# UART_USB.net
KiCad netlist of a schematic drawn in Altium Designer
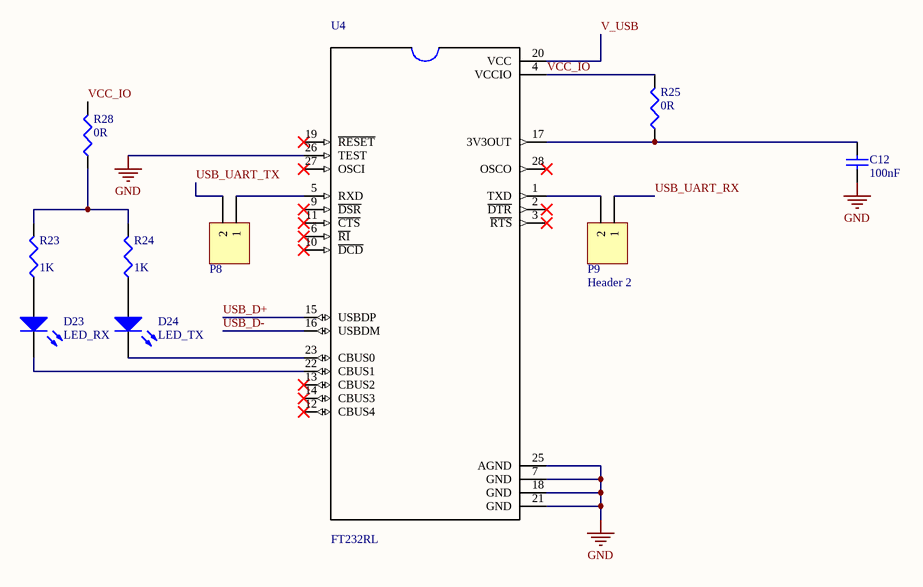
[diagram p0: UART_USB.SchDoc]

(export (version "E")
  (design (tool "Eeschema 10.0.6"))
  (components
    (comp (ref "C12")
      (value "100nF")
      (footprint "1608[0603]")
      (description "CAP CER 0.1UF 16V X7R 0603")
      (fields
        (field (name "DIGI-KEY PART NUMBER") "1276-1258-1-ND")
        (field (name "MANUFACTURER") "Samsung Electro-Mechanics")
        (field (name "PUBLISHER") "Altium Limited")
      )
      (libsource (lib "Miscellaneous Devices") (part "Cap"))
    )
    (comp (ref "D23")
      (value "LED_RX")
      (footprint "1608[0603]")
      (description "LED RED DIFFUSED 0603 SMD")
      (fields
        (field (name "DIGI-KEY PART NUMBER") "475-1195-1-ND")
        (field (name "MANUFACTURER") "OSRAM Opto Semiconductors Inc.")
      )
      (libsource (lib "Miscellaneous Devices") (part "LED2"))
    )
    (comp (ref "D24")
      (value "LED_TX")
      (footprint "1608[0603]")
      (description "LED YELLOW DIFFUSED 0603 SMD")
      (fields
        (field (name "DIGI-KEY PART NUMBER") "475-1196-1-ND")
        (field (name "MANUFACTURER") "OSRAM Opto Semiconductors Inc.")
      )
      (libsource (lib "Miscellaneous Devices") (part "LED2"))
    )
    (comp (ref "P8")
      (value "Header 2")
      (footprint "HDR1X2")
      (description "Header, 2-Pin")
      (fields (field (name "PUBLISHER") "Altium Limited"))
      (libsource (lib "Miscellaneous Connectors") (part "Header 2"))
    )
    (comp (ref "P9")
      (value "Header 2")
      (footprint "HDR1X2")
      (description "Header, 2-Pin")
      (fields (field (name "PUBLISHER") "Altium Limited"))
      (libsource (lib "Miscellaneous Connectors") (part "Header 2"))
    )
    (comp (ref "R23")
      (value "1K")
      (footprint "1608[0603]")
      (description "RES SMD 1K OHM 1% 1/8W 0603")
      (fields
        (field (name "DIGI-KEY PART NUMBER") "MCT0603-1.00K-CFCT-ND")
        (field (name "MANUFACTURER") "Vishay Beyschlag")
      )
      (libsource (lib "Miscellaneous Devices") (part "Res3"))
    )
    (comp (ref "R24")
      (value "1K")
      (footprint "1608[0603]")
      (description "RES SMD 1K OHM 1% 1/8W 0603")
      (fields
        (field (name "DIGI-KEY PART NUMBER") "MCT0603-1.00K-CFCT-ND")
        (field (name "MANUFACTURER") "Vishay Beyschlag")
      )
      (libsource (lib "Miscellaneous Devices") (part "Res3"))
    )
    (comp (ref "R25")
      (value "0R")
      (footprint "C1206")
      (description "RES 0 OHM JUMPER 1/8W 0603")
      (fields
        (field (name "DIGI-KEY PART NUMBER") "749-1745-1-ND")
        (field (name "MANUFACTURER") "Vishay Beyschlag")
      )
      (libsource (lib "Miscellaneous Devices") (part "Res3"))
    )
    (comp (ref "R28")
      (value "0R")
      (footprint "C1206")
      (description "RES 0 OHM JUMPER 1/8W 0603")
      (fields
        (field (name "DIGI-KEY PART NUMBER") "749-1745-1-ND")
        (field (name "MANUFACTURER") "Vishay Beyschlag")
      )
      (libsource (lib "Miscellaneous Devices") (part "Res3"))
    )
    (comp (ref "U4")
      (value "FT232RL")
      (footprint "SOP65P780X200-28N")
      (description "USB Bridge, USB to UART USB 2.0 UART Interface 28-SSOP")
      (fields (field (name "MP") "FT232RL-REEL") (field (name "MF") "FTDI,"))
      (libsource (lib "FT232RL-REEL") (part "FT232RL-REEL"))
    )
  )
  (nets
    (net (code "1") (name "/USB_D+") (class "Default")
      (node (ref "U4") (pin "15") (pinfunction "USBDP_15") (pintype "bidirectional"))
    )
    (net (code "2") (name "/USB_D-") (class "Default")
      (node (ref "U4") (pin "16") (pinfunction "USBDM_16") (pintype "bidirectional"))
    )
    (net (code "3") (name "/USB_UART_RX") (class "Default")
      (node (ref "P9") (pin "1") (pinfunction "1_1") (pintype "passive"))
    )
    (net (code "4") (name "/USB_UART_TX") (class "Default")
      (node (ref "P8") (pin "2") (pinfunction "2_2") (pintype "passive"))
    )
    (net (code "5") (name "/VCC_IO") (class "Default")
      (node (ref "R25") (pin "2") (pinfunction "2_2") (pintype "passive"))
      (node (ref "R28") (pin "2") (pinfunction "2_2") (pintype "passive"))
      (node (ref "U4") (pin "4") (pinfunction "VCCIO_4") (pintype "power_in"))
    )
    (net (code "6") (name "/V_USB") (class "Default")
      (node (ref "U4") (pin "20") (pinfunction "VCC_20") (pintype "power_in"))
    )
    (net (code "7") (name "GND") (class "Default")
      (node (ref "C12") (pin "2") (pinfunction "2_2") (pintype "passive"))
      (node (ref "U4") (pin "18") (pinfunction "GND_18") (pintype "passive"))
      (node (ref "U4") (pin "21") (pinfunction "GND_21") (pintype "passive"))
      (node (ref "U4") (pin "25") (pinfunction "AGND_25") (pintype "passive"))
      (node (ref "U4") (pin "26") (pinfunction "TEST_26") (pintype "input"))
      (node (ref "U4") (pin "7") (pinfunction "GND_7") (pintype "passive"))
    )
    (net (code "8") (name "Net-(D23-A)") (class "Default")
      (node (ref "D23") (pin "1") (pinfunction "A_1") (pintype "passive"))
      (node (ref "R23") (pin "1") (pinfunction "1_1") (pintype "passive"))
    )
    (net (code "9") (name "Net-(D23-K)") (class "Default")
      (node (ref "D23") (pin "2") (pinfunction "K_2") (pintype "passive"))
      (node (ref "U4") (pin "22") (pinfunction "CBUS1_22") (pintype "bidirectional"))
    )
    (net (code "10") (name "Net-(D24-A)") (class "Default")
      (node (ref "D24") (pin "1") (pinfunction "A_1") (pintype "passive"))
      (node (ref "R24") (pin "1") (pinfunction "1_1") (pintype "passive"))
    )
    (net (code "11") (name "Net-(D24-K)") (class "Default")
      (node (ref "D24") (pin "2") (pinfunction "K_2") (pintype "passive"))
      (node (ref "U4") (pin "23") (pinfunction "CBUS0_23") (pintype "bidirectional"))
    )
    (net (code "12") (name "Net-(R23-Pad2)") (class "Default")
      (node (ref "R23") (pin "2") (pinfunction "2_2") (pintype "passive"))
      (node (ref "R24") (pin "2") (pinfunction "2_2") (pintype "passive"))
      (node (ref "R28") (pin "1") (pinfunction "1_1") (pintype "passive"))
    )
    (net (code "13") (name "Net-(U4-3V3OUT)") (class "Default")
      (node (ref "C12") (pin "1") (pinfunction "1_1") (pintype "passive"))
      (node (ref "R25") (pin "1") (pinfunction "1_1") (pintype "passive"))
      (node (ref "U4") (pin "17") (pinfunction "3V3OUT_17") (pintype "output"))
    )
    (net (code "14") (name "Net-(U4-RXD)") (class "Default")
      (node (ref "P8") (pin "1") (pinfunction "1_1") (pintype "passive"))
      (node (ref "U4") (pin "5") (pinfunction "RXD_5") (pintype "input"))
    )
    (net (code "15") (name "Net-(U4-TXD)") (class "Default")
      (node (ref "P9") (pin "2") (pinfunction "2_2") (pintype "passive"))
      (node (ref "U4") (pin "1") (pinfunction "TXD_1") (pintype "output"))
    )
    (net (code "16") (name "unconnected-(U4-CBUS2-Pad13)") (class "Default")
      (node (ref "U4") (pin "13") (pinfunction "CBUS2_13") (pintype "bidirectional+no_connect"))
    )
    (net (code "17") (name "unconnected-(U4-CBUS3-Pad14)") (class "Default")
      (node (ref "U4") (pin "14") (pinfunction "CBUS3_14") (pintype "bidirectional+no_connect"))
    )
    (net (code "18") (name "unconnected-(U4-CBUS4-Pad12)") (class "Default")
      (node (ref "U4") (pin "12") (pinfunction "CBUS4_12") (pintype "bidirectional+no_connect"))
    )
    (net (code "19") (name "unconnected-(U4-OSCI-Pad27)") (class "Default")
      (node (ref "U4") (pin "27") (pinfunction "OSCI_27") (pintype "input+no_connect"))
    )
    (net (code "20") (name "unconnected-(U4-OSCO-Pad28)") (class "Default")
      (node (ref "U4") (pin "28") (pinfunction "OSCO_28") (pintype "output+no_connect"))
    )
    (net (code "21") (name "unconnected-(U4-~{CTS}-Pad11)") (class "Default")
      (node (ref "U4") (pin "11") (pinfunction "~{CTS}_11") (pintype "input+no_connect"))
    )
    (net (code "22") (name "unconnected-(U4-~{DCD}-Pad10)") (class "Default")
      (node (ref "U4") (pin "10") (pinfunction "~{DCD}_10") (pintype "input+no_connect"))
    )
    (net (code "23") (name "unconnected-(U4-~{DSR}-Pad9)") (class "Default")
      (node (ref "U4") (pin "9") (pinfunction "~{DSR}_9") (pintype "input+no_connect"))
    )
    (net (code "24") (name "unconnected-(U4-~{DTR}-Pad2)") (class "Default")
      (node (ref "U4") (pin "2") (pinfunction "~{DTR}_2") (pintype "output+no_connect"))
    )
    (net (code "25") (name "unconnected-(U4-~{RESET}-Pad19)") (class "Default")
      (node (ref "U4") (pin "19") (pinfunction "~{RESET}_19") (pintype "input+no_connect"))
    )
    (net (code "26") (name "unconnected-(U4-~{RI}-Pad6)") (class "Default")
      (node (ref "U4") (pin "6") (pinfunction "~{RI}_6") (pintype "input+no_connect"))
    )
    (net (code "27") (name "unconnected-(U4-~{RTS}-Pad3)") (class "Default")
      (node (ref "U4") (pin "3") (pinfunction "~{RTS}_3") (pintype "output+no_connect"))
    )
  )
)
